# MCU.net
KiCad netlist of a schematic drawn in Altium Designer
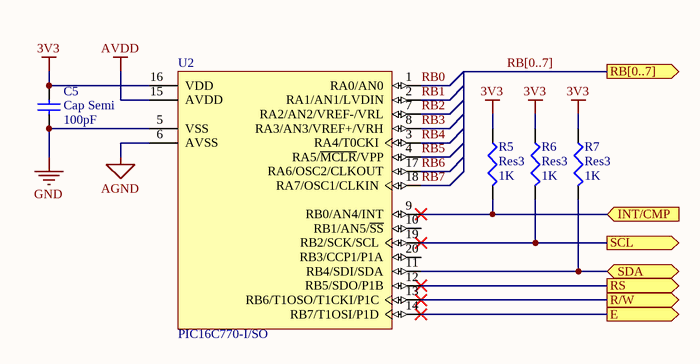
[diagram p0: MCU.SchDoc]

(export (version "E")
  (design (tool "Eeschema 10.0.6"))
  (components
    (comp (ref "C5")
      (value "Cap Semi")
      (footprint "1608[0603]")
      (description "Capacitor (Semiconductor SIM Model)")
      (fields (field (name "ALTIUM_VALUE") "100pF") (field (name "PUBLISHER") "Altium Limited"))
      (libsource (lib "Miscellaneous Devices") (part "Cap Semi"))
    )
    (comp (ref "R5")
      (value "Res3")
      (footprint "J1-0603")
      (description "Resistor")
      (fields (field (name "ALTIUM_VALUE") "1K") (field (name "PUBLISHER") "Altium Limited"))
      (libsource (lib "Miscellaneous Devices") (part "Res3"))
    )
    (comp (ref "R6")
      (value "Res3")
      (footprint "J1-0603")
      (description "Resistor")
      (fields (field (name "ALTIUM_VALUE") "1K") (field (name "PUBLISHER") "Altium Limited"))
      (libsource (lib "Miscellaneous Devices") (part "Res3"))
    )
    (comp (ref "R7")
      (value "Res3")
      (footprint "J1-0603")
      (description "Resistor")
      (fields (field (name "ALTIUM_VALUE") "1K") (field (name "PUBLISHER") "Altium Limited"))
      (libsource (lib "Miscellaneous Devices") (part "Res3"))
    )
    (comp (ref "U2")
      (value "PIC16C770-I/SO")
      (footprint "SOIC-SO20_N")
      (fields (field (name "PUBLISHER") "Altium Limited"))
      (libsource (lib "Microchip Microcontroller 8-Bit PIC16") (part "PIC16C770-I/SO"))
    )
  )
  (nets
    (net (code "1") (name "/E") (class "Default")
      (node (ref "U2") (pin "14") (pinfunction "RB7/T1OSI/P1D_14") (pintype "bidirectional+no_connect"))
    )
    (net (code "2") (name "/INT{slash}CMP") (class "Default")
      (node (ref "R5") (pin "2") (pinfunction "2_2") (pintype "passive"))
      (node (ref "U2") (pin "9") (pinfunction "RB0/AN4/INT_9") (pintype "bidirectional"))
    )
    (net (code "3") (name "/RB0") (class "Default")
      (node (ref "U2") (pin "1") (pinfunction "RA0/AN0_1") (pintype "bidirectional"))
    )
    (net (code "4") (name "/RB1") (class "Default")
      (node (ref "U2") (pin "2") (pinfunction "RA1/AN1/LVDIN_2") (pintype "bidirectional"))
    )
    (net (code "5") (name "/RB2") (class "Default")
      (node (ref "U2") (pin "7") (pinfunction "RA2/AN2/VREF-/VRL_7") (pintype "bidirectional"))
    )
    (net (code "6") (name "/RB3") (class "Default")
      (node (ref "U2") (pin "8") (pinfunction "RA3/AN3/VREF+/VRH_8") (pintype "bidirectional"))
    )
    (net (code "7") (name "/RB4") (class "Default")
      (node (ref "U2") (pin "3") (pinfunction "RA4/T0CKI_3") (pintype "bidirectional"))
    )
    (net (code "8") (name "/RB5") (class "Default")
      (node (ref "U2") (pin "4") (pinfunction "RA5/~{MCLR}/VPP_4") (pintype "bidirectional"))
    )
    (net (code "9") (name "/RB6") (class "Default")
      (node (ref "U2") (pin "17") (pinfunction "RA6/OSC2/CLKOUT_17") (pintype "bidirectional"))
    )
    (net (code "10") (name "/RB7") (class "Default")
      (node (ref "U2") (pin "18") (pinfunction "RA7/OSC1/CLKIN_18") (pintype "bidirectional"))
    )
    (net (code "12") (name "/RS") (class "Default")
      (node (ref "U2") (pin "12") (pinfunction "RB5/SDO/P1B_12") (pintype "bidirectional+no_connect"))
    )
    (net (code "13") (name "/R{slash}W") (class "Default")
      (node (ref "U2") (pin "13") (pinfunction "RB6/T1OSO/T1CKI/P1C_13") (pintype "bidirectional+no_connect"))
    )
    (net (code "14") (name "/SCL") (class "Default")
      (node (ref "R6") (pin "2") (pinfunction "2_2") (pintype "passive"))
      (node (ref "U2") (pin "19") (pinfunction "RB2/SCK/SCL_19") (pintype "bidirectional"))
    )
    (net (code "15") (name "/SDA") (class "Default")
      (node (ref "R7") (pin "2") (pinfunction "2_2") (pintype "passive"))
      (node (ref "U2") (pin "11") (pinfunction "RB4/SDI/SDA_11") (pintype "bidirectional"))
    )
    (net (code "16") (name "3V3") (class "Default")
      (node (ref "C5") (pin "2") (pinfunction "2_2") (pintype "passive"))
      (node (ref "R5") (pin "1") (pinfunction "1_1") (pintype "passive"))
      (node (ref "R6") (pin "1") (pinfunction "1_1") (pintype "passive"))
      (node (ref "R7") (pin "1") (pinfunction "1_1") (pintype "passive"))
      (node (ref "U2") (pin "16") (pinfunction "VDD_16") (pintype "power_in"))
    )
    (net (code "17") (name "AGND") (class "Default")
      (node (ref "U2") (pin "6") (pinfunction "AVSS_6") (pintype "power_in"))
    )
    (net (code "18") (name "AVDD") (class "Default")
      (node (ref "U2") (pin "15") (pinfunction "AVDD_15") (pintype "power_in"))
    )
    (net (code "19") (name "GND") (class "Default")
      (node (ref "C5") (pin "1") (pinfunction "1_1") (pintype "passive"))
      (node (ref "U2") (pin "5") (pinfunction "VSS_5") (pintype "power_in"))
    )
    (net (code "20") (name "unconnected-(U2-RB1{slash}AN5{slash}~{SS}-Pad10)") (class "Default")
      (node (ref "U2") (pin "10") (pinfunction "RB1/AN5/~{SS}_10") (pintype "bidirectional"))
    )
    (net (code "21") (name "unconnected-(U2-RB3{slash}CCP1{slash}P1A-Pad20)") (class "Default")
      (node (ref "U2") (pin "20") (pinfunction "RB3/CCP1/P1A_20") (pintype "bidirectional"))
    )
  )
)
